# Anchor_G431.net
KiCad netlist of a schematic drawn in Altium Designer
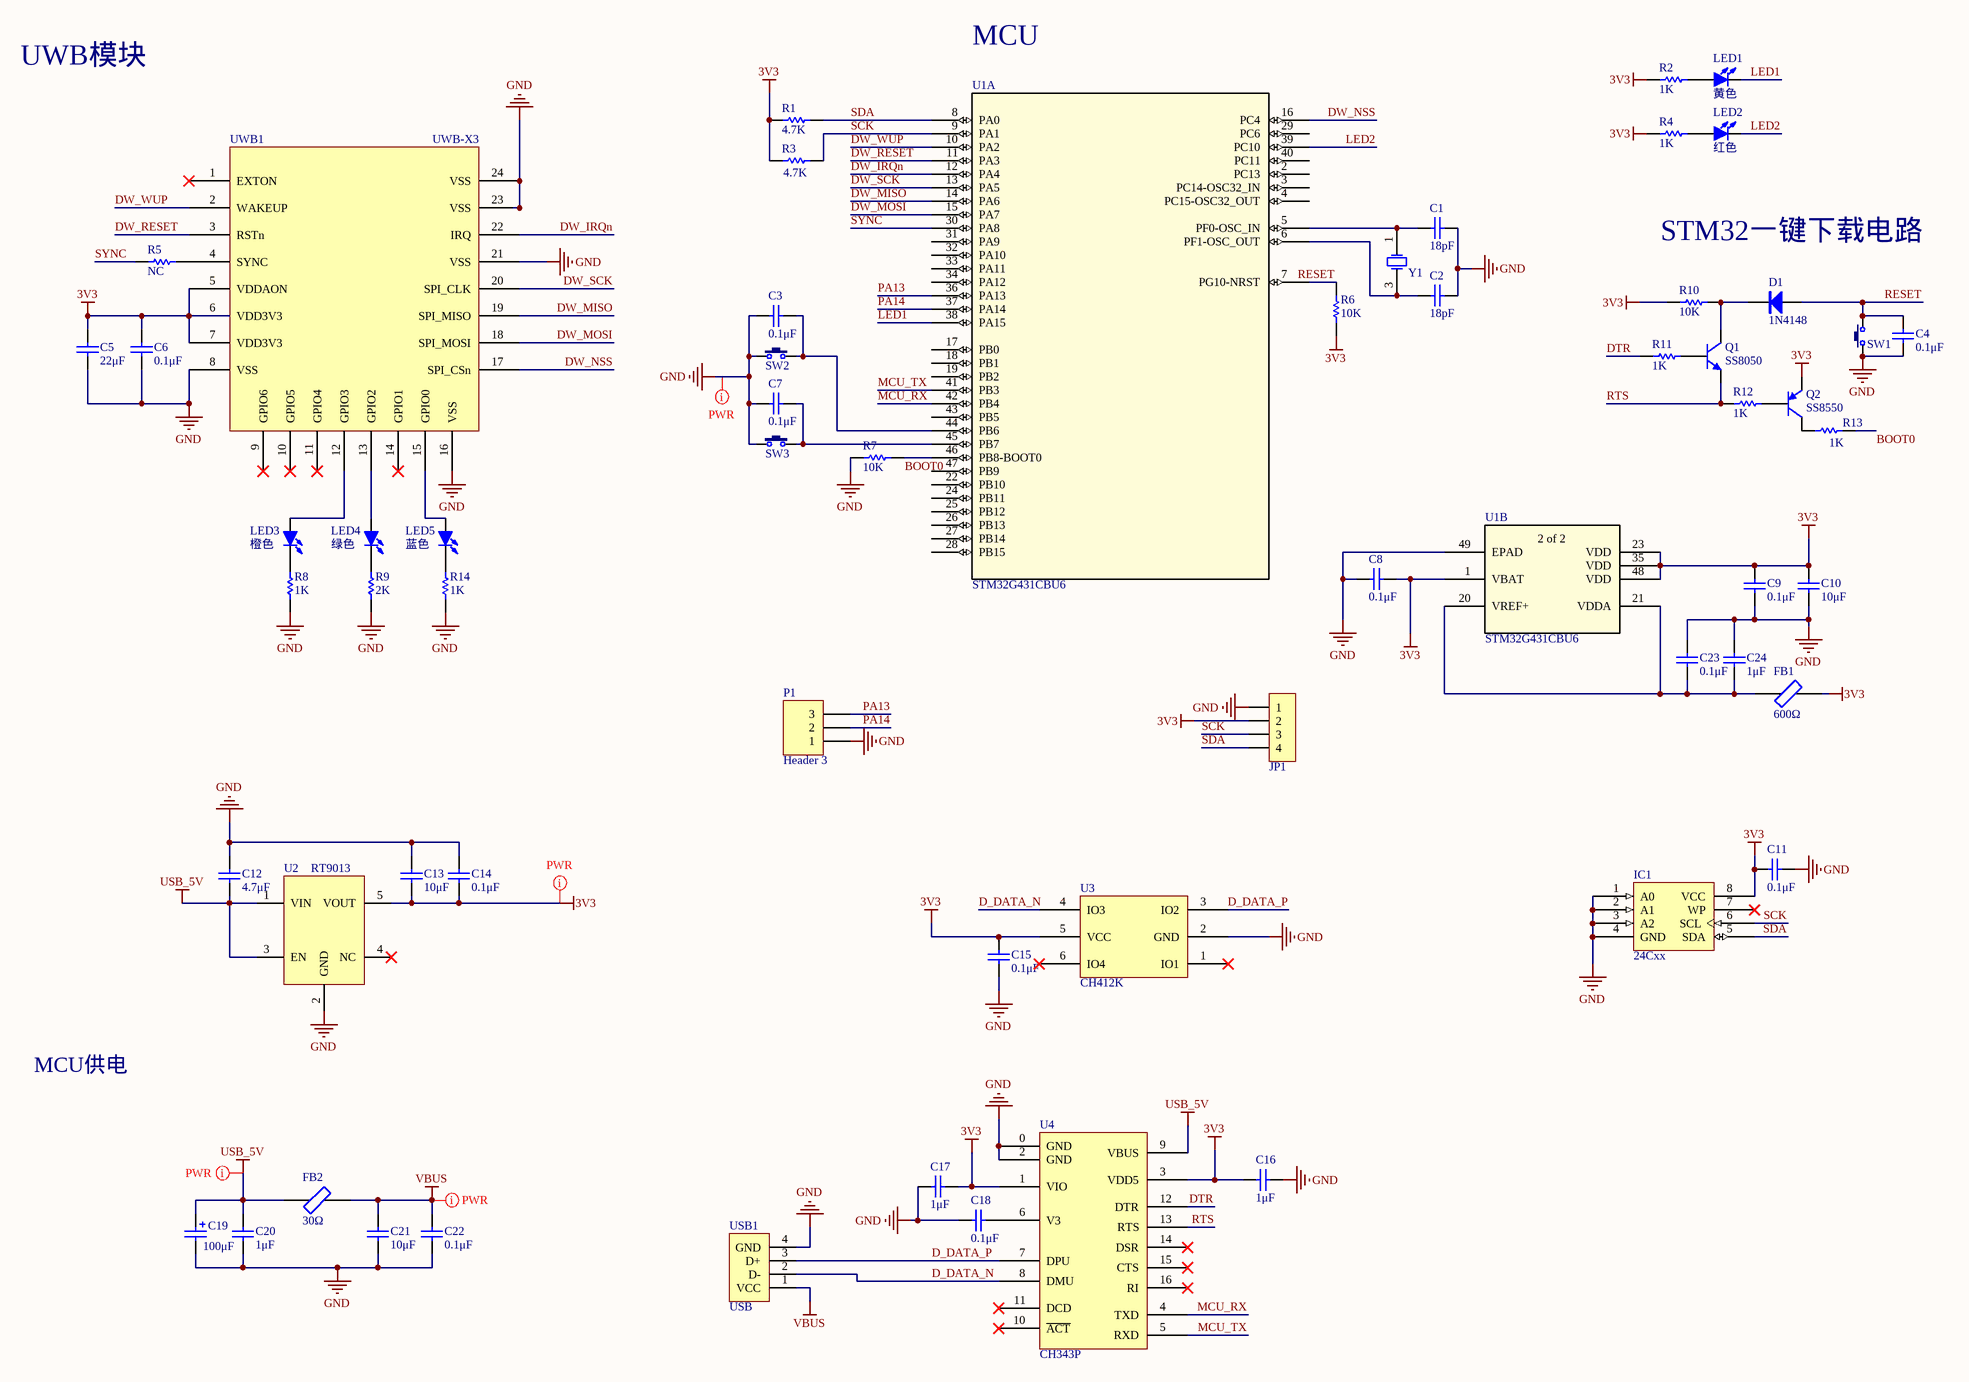
[diagram p0: Anchor_G431.SchDoc]

(export (version "E")
  (design (tool "Eeschema 10.0.6"))
  (components
    (comp (ref "C1")
      (value "18pF")
      (footprint "C 0603_L")
      (description "Capacitor")
      (fields (field (name "Comment") "Cap") (field (name "PUBLISHER") "Altium Limited"))
      (libsource (lib "Nixie") (part "Cap"))
    )
    (comp (ref "C2")
      (value "18pF")
      (footprint "C 0603_L")
      (description "Capacitor")
      (fields (field (name "Comment") "Cap") (field (name "PUBLISHER") "Altium Limited"))
      (libsource (lib "Nixie") (part "Cap"))
    )
    (comp (ref "C3")
      (value "0.1μF")
      (footprint "C 0603_L")
      (description "Capacitor")
      (fields (field (name "Comment") "Cap") (field (name "PUBLISHER") "Altium Limited"))
      (libsource (lib "Nixie") (part "Cap"))
    )
    (comp (ref "C4")
      (value "0.1μF")
      (footprint "C 0603_L")
      (description "Capacitor")
      (fields (field (name "Comment") "Cap") (field (name "PUBLISHER") "Altium Limited"))
      (libsource (lib "Nixie") (part "Cap"))
    )
    (comp (ref "C5")
      (value "22μF")
      (footprint "C 0603_L")
      (description "Capacitor")
      (fields (field (name "Comment") "Cap") (field (name "PUBLISHER") "Altium Limited"))
      (libsource (lib "Nixie") (part "Cap"))
    )
    (comp (ref "C6")
      (value "0.1μF")
      (footprint "C 0603_L")
      (description "Capacitor")
      (fields (field (name "Comment") "Cap") (field (name "PUBLISHER") "Altium Limited"))
      (libsource (lib "Nixie") (part "Cap"))
    )
    (comp (ref "C7")
      (value "0.1μF")
      (footprint "C 0603_L")
      (description "Capacitor")
      (fields (field (name "Comment") "Cap") (field (name "PUBLISHER") "Altium Limited"))
      (libsource (lib "Nixie") (part "Cap"))
    )
    (comp (ref "C8")
      (value "0.1μF")
      (footprint "C 0603_L")
      (description "Capacitor")
      (fields (field (name "Comment") "Cap") (field (name "PUBLISHER") "Altium Limited"))
      (libsource (lib "Nixie") (part "Cap"))
    )
    (comp (ref "C9")
      (value "0.1μF")
      (footprint "C 0603_L")
      (description "Capacitor")
      (fields (field (name "Comment") "Cap") (field (name "PUBLISHER") "Altium Limited"))
      (libsource (lib "Nixie") (part "Cap"))
    )
    (comp (ref "C10")
      (value "10μF")
      (footprint "C 0603_L")
      (description "Capacitor")
      (fields (field (name "Comment") "Cap") (field (name "PUBLISHER") "Altium Limited"))
      (libsource (lib "Nixie") (part "Cap"))
    )
    (comp (ref "C11")
      (value "0.1μF")
      (footprint "C 0603_L")
      (description "Capacitor")
      (fields (field (name "Comment") "Cap") (field (name "PUBLISHER") "Altium Limited"))
      (libsource (lib "Nixie") (part "Cap"))
    )
    (comp (ref "C12")
      (value "4.7μF")
      (footprint "C 0603_L")
      (description "Capacitor")
      (fields (field (name "Comment") "Cap") (field (name "PUBLISHER") "Altium Limited"))
      (libsource (lib "Nixie") (part "Cap"))
    )
    (comp (ref "C13")
      (value "10μF")
      (footprint "C 0603_L")
      (description "Capacitor")
      (fields (field (name "Comment") "Cap") (field (name "PUBLISHER") "Altium Limited"))
      (libsource (lib "Nixie") (part "Cap"))
    )
    (comp (ref "C14")
      (value "0.1μF")
      (footprint "C 0603_L")
      (description "Capacitor")
      (fields (field (name "Comment") "Cap") (field (name "PUBLISHER") "Altium Limited"))
      (libsource (lib "Nixie") (part "Cap"))
    )
    (comp (ref "C15")
      (value "0.1μF")
      (footprint "C 0603_L")
      (description "Capacitor")
      (fields (field (name "Comment") "Cap") (field (name "PUBLISHER") "Altium Limited"))
      (libsource (lib "Nixie") (part "Cap"))
    )
    (comp (ref "C16")
      (value "1μF")
      (footprint "C 0603_L")
      (description "Capacitor")
      (fields (field (name "Comment") "Cap") (field (name "PUBLISHER") "Altium Limited"))
      (libsource (lib "Nixie") (part "Cap"))
    )
    (comp (ref "C17")
      (value "1μF")
      (footprint "C 0603_L")
      (description "Capacitor")
      (fields (field (name "Comment") "Cap") (field (name "PUBLISHER") "Altium Limited"))
      (libsource (lib "Nixie") (part "Cap"))
    )
    (comp (ref "C18")
      (value "0.1μF")
      (footprint "C 0603_L")
      (description "Capacitor")
      (fields (field (name "Comment") "Cap") (field (name "PUBLISHER") "Altium Limited"))
      (libsource (lib "Nixie") (part "Cap"))
    )
    (comp (ref "C19")
      (value "100μF")
      (footprint "CM C(5*5.4)")
      (description "Polarized Capacitor (Radial)")
      (fields (field (name "Comment") "Cap Pol1") (field (name "PUBLISHER") "Altium Limited"))
      (libsource (lib "Nixie") (part "Cap Pol1"))
    )
    (comp (ref "C20")
      (value "1μF")
      (footprint "C 0603_L")
      (description "Capacitor")
      (fields (field (name "Comment") "Cap") (field (name "PUBLISHER") "Altium Limited"))
      (libsource (lib "Nixie") (part "Cap"))
    )
    (comp (ref "C21")
      (value "10μF")
      (footprint "C 0603_L")
      (description "Capacitor")
      (fields (field (name "Comment") "Cap") (field (name "PUBLISHER") "Altium Limited"))
      (libsource (lib "Nixie") (part "Cap"))
    )
    (comp (ref "C22")
      (value "0.1μF")
      (footprint "C 0603_L")
      (description "Capacitor")
      (fields (field (name "Comment") "Cap") (field (name "PUBLISHER") "Altium Limited"))
      (libsource (lib "Nixie") (part "Cap"))
    )
    (comp (ref "C23")
      (value "0.1μF")
      (footprint "C 0603_L")
      (description "Capacitor")
      (fields (field (name "Comment") "Cap") (field (name "PUBLISHER") "Altium Limited"))
      (libsource (lib "Nixie") (part "Cap"))
    )
    (comp (ref "C24")
      (value "1μF")
      (footprint "C 0603_L")
      (description "Capacitor")
      (fields (field (name "Comment") "Cap") (field (name "PUBLISHER") "Altium Limited"))
      (libsource (lib "Nixie") (part "Cap"))
    )
    (comp (ref "D1")
      (value "1N4148")
      (footprint "SOD-323")
      (description "开关二极管")
      (libsource (lib "Nixie") (part "1N4148"))
    )
    (comp (ref "FB1")
      (value "600Ω")
      (footprint "C 0603_L")
      (description "铁氧体磁珠")
      (fields (field (name "Comment") "Ferrite bead"))
      (libsource (lib "Nixie") (part "Ferrite bead"))
    )
    (comp (ref "FB2")
      (value "30Ω")
      (footprint "C 0603_L")
      (description "铁氧体磁珠")
      (fields (field (name "Comment") "Ferrite bead"))
      (libsource (lib "Nixie") (part "Ferrite bead"))
    )
    (comp (ref "IC1")
      (value "24Cxx")
      (footprint "SOP8_L")
      (description "外置EEPROM")
      (fields (field (name "版权归属") "封装库来自淘宝 ID：黄晶宝石"))
      (libsource (lib "Nixie") (part "24Cxx"))
    )
    (comp (ref "JP1")
      (value "HDR-1X4")
      (footprint "HDR2.54-LI-4P")
      (description "4P接插件")
      (fields (field (name "版权归属") "封装库来自淘宝 ID：黄晶宝石"))
      (libsource (lib "Nixie") (part "Header 4"))
    )
    (comp (ref "LED1")
      (value "黄色")
      (footprint "LED 0805G")
      (description "贴片LED")
      (fields (field (name "版权归属") "封装库来自淘宝 ID：黄晶宝石"))
      (libsource (lib "Nixie") (part "LED-SMD"))
    )
    (comp (ref "LED2")
      (value "红色")
      (footprint "LED 0805R")
      (description "贴片LED")
      (fields (field (name "版权归属") "封装库来自淘宝 ID：黄晶宝石"))
      (libsource (lib "Nixie") (part "LED-SMD"))
    )
    (comp (ref "LED3")
      (value "橙色")
      (footprint "LED 0805G")
      (description "贴片LED")
      (fields (field (name "版权归属") "封装库来自淘宝 ID：黄晶宝石"))
      (libsource (lib "Nixie") (part "LED-SMD"))
    )
    (comp (ref "LED4")
      (value "绿色")
      (footprint "LED 0805G")
      (description "贴片LED")
      (fields (field (name "版权归属") "封装库来自淘宝 ID：黄晶宝石"))
      (libsource (lib "Nixie") (part "LED-SMD"))
    )
    (comp (ref "LED5")
      (value "蓝色")
      (footprint "LED 0805G")
      (description "贴片LED")
      (fields (field (name "版权归属") "封装库来自淘宝 ID：黄晶宝石"))
      (libsource (lib "Nixie") (part "LED-SMD"))
    )
    (comp (ref "P1")
      (value "Header 3")
      (footprint "HDR2.54-LI-3P")
      (description "Header, 3-Pin")
      (fields (field (name "PUBLISHER") "Altium Limited"))
      (libsource (lib "Miscellaneous Connectors") (part "Header 3"))
    )
    (comp (ref "Q1")
      (value "SS8050")
      (footprint "SOT-23-3L")
      (description "高频放大-NPN型")
      (fields (field (name "版权归属") "封装库来自淘宝 ID：黄晶宝石"))
      (libsource (lib "Nixie") (part "8050-SMD"))
    )
    (comp (ref "Q2")
      (value "SS8550")
      (footprint "SOT-23-3L")
      (description "高频放大-PNP型")
      (fields (field (name "版权归属") "封装库来自淘宝 ID：黄晶宝石"))
      (libsource (lib "Nixie") (part "8550-SMD"))
    )
    (comp (ref "R1")
      (value "4.7K")
      (footprint "R 0603_L")
      (description "Resistor")
      (fields (field (name "PUBLISHER") "Altium Limited"))
      (libsource (lib "Nixie") (part "Resistor"))
    )
    (comp (ref "R2")
      (value "1K")
      (footprint "R 0603_L")
      (description "Resistor")
      (fields (field (name "PUBLISHER") "Altium Limited"))
      (libsource (lib "Nixie") (part "Resistor"))
    )
    (comp (ref "R3")
      (value "4.7K")
      (footprint "R 0603_L")
      (description "Resistor")
      (fields (field (name "PUBLISHER") "Altium Limited"))
      (libsource (lib "Nixie") (part "Resistor"))
    )
    (comp (ref "R4")
      (value "1K")
      (footprint "R 0603_L")
      (description "Resistor")
      (fields (field (name "PUBLISHER") "Altium Limited"))
      (libsource (lib "Nixie") (part "Resistor"))
    )
    (comp (ref "R5")
      (value "NC")
      (footprint "R 0603_L")
      (description "Resistor")
      (fields (field (name "PUBLISHER") "Altium Limited"))
      (libsource (lib "Nixie") (part "Resistor"))
    )
    (comp (ref "R6")
      (value "10K")
      (footprint "R 0603_L")
      (description "Resistor")
      (fields (field (name "PUBLISHER") "Altium Limited"))
      (libsource (lib "Nixie") (part "Resistor"))
    )
    (comp (ref "R7")
      (value "10K")
      (footprint "R 0603_L")
      (description "Resistor")
      (fields (field (name "PUBLISHER") "Altium Limited"))
      (libsource (lib "Nixie") (part "Resistor"))
    )
    (comp (ref "R8")
      (value "1K")
      (footprint "R 0603_L")
      (description "Resistor")
      (fields (field (name "PUBLISHER") "Altium Limited"))
      (libsource (lib "Nixie") (part "Resistor"))
    )
    (comp (ref "R9")
      (value "2K")
      (footprint "R 0603_L")
      (description "Resistor")
      (fields (field (name "PUBLISHER") "Altium Limited"))
      (libsource (lib "Nixie") (part "Resistor"))
    )
    (comp (ref "R10")
      (value "10K")
      (footprint "R 0603_L")
      (description "Resistor")
      (fields (field (name "PUBLISHER") "Altium Limited"))
      (libsource (lib "Nixie") (part "Resistor"))
    )
    (comp (ref "R11")
      (value "1K")
      (footprint "R 0603_L")
      (description "Resistor")
      (fields (field (name "PUBLISHER") "Altium Limited"))
      (libsource (lib "Nixie") (part "Resistor"))
    )
    (comp (ref "R12")
      (value "1K")
      (footprint "R 0603_L")
      (description "Resistor")
      (fields (field (name "PUBLISHER") "Altium Limited"))
      (libsource (lib "Nixie") (part "Resistor"))
    )
    (comp (ref "R13")
      (value "1K")
      (footprint "R 0603_L")
      (description "Resistor")
      (fields (field (name "PUBLISHER") "Altium Limited"))
      (libsource (lib "Nixie") (part "Resistor"))
    )
    (comp (ref "R14")
      (value "1K")
      (footprint "R 0603_L")
      (description "Resistor")
      (fields (field (name "PUBLISHER") "Altium Limited"))
      (libsource (lib "Nixie") (part "Resistor"))
    )
    (comp (ref "SW1")
      (value "3x6x5")
      (footprint "TSW SMD-3*6*2.5")
      (description "3x6轻触开关")
      (fields (field (name "版权归属") "封装库来自淘宝 ID：黄晶宝石"))
      (libsource (lib "Nixie") (part "TSW 3x6"))
    )
    (comp (ref "SW2")
      (value "3x6x5")
      (footprint "TSW SMD-3*6*2.5")
      (description "3x6轻触开关")
      (fields (field (name "版权归属") "封装库来自淘宝 ID：黄晶宝石"))
      (libsource (lib "") (part "TSW 3x6_1"))
    )
    (comp (ref "SW3")
      (value "3x6x5")
      (footprint "TSW SMD-3*6*2.5")
      (description "3x6轻触开关")
      (fields (field (name "版权归属") "封装库来自淘宝 ID：黄晶宝石"))
      (libsource (lib "") (part "TSW 3x6_1"))
    )
    (comp (ref "U1")
      (value "STM32G431CBU6")
      (footprint "UFQFPN-48_7X7X0P55MM")
      (description "No Description Available")
      (fields (field (name "COPYRIGHT") "Copyright (C) 2023 Ultra Librarian. All rights reserved."))
      (libsource (lib "Nixie") (part "STM32G431CBU6"))
    )
    (comp (ref "U2")
      (value "RT9013")
      (footprint "SOT23-5L")
      (description "LDO")
      (libsource (lib "HandHeld_terminal") (part "RT9013"))
    )
    (comp (ref "U3")
      (value "CH412K")
      (footprint "SOT-363")
      (description "四路ESD保护")
      (libsource (lib "Nixie") (part "CH412K"))
    )
    (comp (ref "U4")
      (value "CH343P")
      (footprint "QFN16")
      (description "USB转串口")
      (libsource (lib "Nixie") (part "CH343"))
    )
    (comp (ref "USB1")
      (value "USB")
      (footprint "USB_A/P_B")
      (description "USB-A型公接口")
      (fields (field (name "版权归属") "封装库来自淘宝卖家 ID：黄晶宝石"))
      (libsource (lib "Nixie") (part "USB-A/P"))
    )
    (comp (ref "UWB1")
      (value "UWB-X3")
      (footprint "UWB-X3-MAX-IPEX")
      (libsource (lib "Nixie") (part "UWB-X3(DWM3000)"))
    )
    (comp (ref "Y1")
      (value "8MHz ±20ppm 20pF")
      (footprint "OSC 3225-4P")
      (description "贴片晶振")
      (libsource (lib "HandHeld_terminal") (part "SMD-5032_2P 8MHz 20ppm 20pF"))
    )
  )
  (nets
    (net (code "1") (name "/BOOT0") (class "Default")
      (node (ref "R13") (pin "2") (pinfunction "2_2") (pintype "passive"))
      (node (ref "R7") (pin "2") (pinfunction "2_2") (pintype "passive"))
      (node (ref "U1") (pin "46") (pinfunction "PB8-BOOT0_46") (pintype "bidirectional"))
    )
    (net (code "2") (name "/DTR") (class "Default")
      (node (ref "R11") (pin "1") (pinfunction "1_1") (pintype "passive"))
      (node (ref "U4") (pin "12") (pinfunction "DTR_12") (pintype "passive"))
    )
    (net (code "3") (name "/DW_IRQn") (class "Default")
      (node (ref "U1") (pin "12") (pinfunction "PA4_12") (pintype "bidirectional"))
      (node (ref "UWB1") (pin "22") (pinfunction "IRQ_22") (pintype "passive"))
    )
    (net (code "4") (name "/DW_MISO") (class "Default")
      (node (ref "U1") (pin "14") (pinfunction "PA6_14") (pintype "bidirectional"))
      (node (ref "UWB1") (pin "19") (pinfunction "SPI_MISO_19") (pintype "passive"))
    )
    (net (code "5") (name "/DW_MOSI") (class "Default")
      (node (ref "U1") (pin "15") (pinfunction "PA7_15") (pintype "bidirectional"))
      (node (ref "UWB1") (pin "18") (pinfunction "SPI_MOSI_18") (pintype "passive"))
    )
    (net (code "6") (name "/DW_NSS") (class "Default")
      (node (ref "U1") (pin "16") (pinfunction "PC4_16") (pintype "bidirectional"))
      (node (ref "UWB1") (pin "17") (pinfunction "SPI_CSn_17") (pintype "passive"))
    )
    (net (code "7") (name "/DW_RESET") (class "Default")
      (node (ref "U1") (pin "11") (pinfunction "PA3_11") (pintype "bidirectional"))
      (node (ref "UWB1") (pin "3") (pinfunction "RSTn_3") (pintype "passive"))
    )
    (net (code "8") (name "/DW_SCK") (class "Default")
      (node (ref "U1") (pin "13") (pinfunction "PA5_13") (pintype "bidirectional"))
      (node (ref "UWB1") (pin "20") (pinfunction "SPI_CLK_20") (pintype "passive"))
    )
    (net (code "9") (name "/DW_WUP") (class "Default")
      (node (ref "U1") (pin "10") (pinfunction "PA2_10") (pintype "bidirectional"))
      (node (ref "UWB1") (pin "2") (pinfunction "WAKEUP_2") (pintype "passive"))
    )
    (net (code "10") (name "/D_DATA_N") (class "Default")
      (node (ref "U3") (pin "4") (pinfunction "IO3_4") (pintype "passive"))
      (node (ref "U4") (pin "8") (pinfunction "DMU_8") (pintype "passive"))
      (node (ref "USB1") (pin "2") (pinfunction "D-_2") (pintype "passive"))
    )
    (net (code "11") (name "/D_DATA_P") (class "Default")
      (node (ref "U3") (pin "3") (pinfunction "IO2_3") (pintype "passive"))
      (node (ref "U4") (pin "7") (pinfunction "DPU_7") (pintype "passive"))
      (node (ref "USB1") (pin "3") (pinfunction "D+_3") (pintype "passive"))
    )
    (net (code "12") (name "/LED1") (class "Default")
      (node (ref "LED1") (pin "2") (pinfunction "K_2") (pintype "passive"))
      (node (ref "U1") (pin "38") (pinfunction "PA15_38") (pintype "bidirectional"))
    )
    (net (code "13") (name "/LED2") (class "Default")
      (node (ref "LED2") (pin "2") (pinfunction "K_2") (pintype "passive"))
      (node (ref "U1") (pin "39") (pinfunction "PC10_39") (pintype "bidirectional"))
    )
    (net (code "14") (name "/MCU_RX") (class "Default")
      (node (ref "U1") (pin "42") (pinfunction "PB4_42") (pintype "bidirectional"))
      (node (ref "U4") (pin "4") (pinfunction "TXD_4") (pintype "passive"))
    )
    (net (code "15") (name "/MCU_TX") (class "Default")
      (node (ref "U1") (pin "41") (pinfunction "PB3_41") (pintype "bidirectional"))
      (node (ref "U4") (pin "5") (pinfunction "RXD_5") (pintype "passive"))
    )
    (net (code "16") (name "/PA13") (class "Default")
      (node (ref "P1") (pin "3") (pinfunction "3_3") (pintype "passive"))
      (node (ref "U1") (pin "36") (pinfunction "PA13_36") (pintype "bidirectional"))
    )
    (net (code "17") (name "/PA14") (class "Default")
      (node (ref "P1") (pin "2") (pinfunction "2_2") (pintype "passive"))
      (node (ref "U1") (pin "37") (pinfunction "PA14_37") (pintype "bidirectional"))
    )
    (net (code "18") (name "/RESET") (class "Default")
      (node (ref "C4") (pin "2") (pinfunction "2_2") (pintype "passive"))
      (node (ref "D1") (pin "1") (pinfunction "A_1") (pintype "passive"))
      (node (ref "R6") (pin "1") (pinfunction "1_1") (pintype "passive"))
      (node (ref "SW1") (pin "2") (pinfunction "2_2") (pintype "passive"))
      (node (ref "U1") (pin "7") (pinfunction "PG10-NRST_7") (pintype "bidirectional"))
    )
    (net (code "19") (name "/RTS") (class "Default")
      (node (ref "Q1") (pin "2") (pinfunction "E_2") (pintype "passive"))
      (node (ref "R12") (pin "1") (pinfunction "1_1") (pintype "passive"))
      (node (ref "U4") (pin "13") (pinfunction "RTS_13") (pintype "passive"))
    )
    (net (code "20") (name "/SCK") (class "Default")
      (node (ref "IC1") (pin "6") (pinfunction "SCL_6") (pintype "input"))
      (node (ref "JP1") (pin "3") (pinfunction "3_3") (pintype "passive"))
      (node (ref "R3") (pin "2") (pinfunction "2_2") (pintype "passive"))
      (node (ref "U1") (pin "9") (pinfunction "PA1_9") (pintype "bidirectional"))
    )
    (net (code "21") (name "/SDA") (class "Default")
      (node (ref "IC1") (pin "5") (pinfunction "SDA_5") (pintype "bidirectional"))
      (node (ref "JP1") (pin "4") (pinfunction "4_4") (pintype "passive"))
      (node (ref "R1") (pin "2") (pinfunction "2_2") (pintype "passive"))
      (node (ref "U1") (pin "8") (pinfunction "PA0_8") (pintype "bidirectional"))
    )
    (net (code "22") (name "/SYNC") (class "Default")
      (node (ref "R5") (pin "1") (pinfunction "1_1") (pintype "passive"))
      (node (ref "U1") (pin "30") (pinfunction "PA8_30") (pintype "bidirectional"))
    )
    (net (code "23") (name "3V3") (class "Default")
      (node (ref "C10") (pin "2") (pinfunction "2_2") (pintype "passive"))
      (node (ref "C11") (pin "2") (pinfunction "2_2") (pintype "passive"))
      (node (ref "C13") (pin "1") (pinfunction "1_1") (pintype "passive"))
      (node (ref "C14") (pin "1") (pinfunction "1_1") (pintype "passive"))
      (node (ref "C15") (pin "2") (pinfunction "2_2") (pintype "passive"))
      (node (ref "C16") (pin "1") (pinfunction "1_1") (pintype "passive"))
      (node (ref "C17") (pin "2") (pinfunction "2_2") (pintype "passive"))
      (node (ref "C5") (pin "2") (pinfunction "2_2") (pintype "passive"))
      (node (ref "C6") (pin "1") (pinfunction "1_1") (pintype "passive"))
      (node (ref "C8") (pin "1") (pinfunction "1_1") (pintype "passive"))
      (node (ref "C9") (pin "2") (pinfunction "2_2") (pintype "passive"))
      (node (ref "FB1") (pin "2") (pinfunction "2_2") (pintype "passive"))
      (node (ref "IC1") (pin "8") (pinfunction "VCC_8") (pintype "power_in"))
      (node (ref "JP1") (pin "2") (pinfunction "2_2") (pintype "passive"))
      (node (ref "Q2") (pin "2") (pinfunction "E_2") (pintype "passive"))
      (node (ref "R1") (pin "1") (pinfunction "1_1") (pintype "passive"))
      (node (ref "R10") (pin "1") (pinfunction "1_1") (pintype "passive"))
      (node (ref "R2") (pin "2") (pinfunction "2_2") (pintype "passive"))
      (node (ref "R3") (pin "1") (pinfunction "1_1") (pintype "passive"))
      (node (ref "R4") (pin "2") (pinfunction "2_2") (pintype "passive"))
      (node (ref "R6") (pin "2") (pinfunction "2_2") (pintype "passive"))
      (node (ref "U1") (pin "1") (pinfunction "VBAT_1") (pintype "power_in"))
      (node (ref "U1") (pin "23") (pinfunction "VDD_23") (pintype "power_in"))
      (node (ref "U1") (pin "35") (pinfunction "VDD_35") (pintype "power_in"))
      (node (ref "U1") (pin "48") (pinfunction "VDD_48") (pintype "power_in"))
      (node (ref "U2") (pin "5") (pinfunction "VOUT_5") (pintype "passive"))
      (node (ref "U3") (pin "5") (pinfunction "VCC_5") (pintype "passive"))
      (node (ref "U4") (pin "1") (pinfunction "VIO_1") (pintype "passive"))
      (node (ref "U4") (pin "3") (pinfunction "VDD5_3") (pintype "passive"))
      (node (ref "UWB1") (pin "5") (pinfunction "VDDAON_5") (pintype "passive"))
      (node (ref "UWB1") (pin "6") (pinfunction "VDD3V3_6") (pintype "passive"))
      (node (ref "UWB1") (pin "7") (pinfunction "VDD3V3_7") (pintype "passive"))
    )
    (net (code "24") (name "GND") (class "Default")
      (node (ref "C1") (pin "1") (pinfunction "1_1") (pintype "passive"))
      (node (ref "C10") (pin "1") (pinfunction "1_1") (pintype "passive"))
      (node (ref "C11") (pin "1") (pinfunction "1_1") (pintype "passive"))
      (node (ref "C12") (pin "2") (pinfunction "2_2") (pintype "passive"))
      (node (ref "C13") (pin "2") (pinfunction "2_2") (pintype "passive"))
      (node (ref "C14") (pin "2") (pinfunction "2_2") (pintype "passive"))
      (node (ref "C15") (pin "1") (pinfunction "1_1") (pintype "passive"))
      (node (ref "C16") (pin "2") (pinfunction "2_2") (pintype "passive"))
      (node (ref "C17") (pin "1") (pinfunction "1_1") (pintype "passive"))
      (node (ref "C18") (pin "1") (pinfunction "1_1") (pintype "passive"))
      (node (ref "C19") (pin "2") (pinfunction "2_2") (pintype "passive"))
      (node (ref "C2") (pin "1") (pinfunction "1_1") (pintype "passive"))
      (node (ref "C20") (pin "1") (pinfunction "1_1") (pintype "passive"))
      (node (ref "C21") (pin "1") (pinfunction "1_1") (pintype "passive"))
      (node (ref "C22") (pin "1") (pinfunction "1_1") (pintype "passive"))
      (node (ref "C23") (pin "2") (pinfunction "2_2") (pintype "passive"))
      (node (ref "C24") (pin "2") (pinfunction "2_2") (pintype "passive"))
      (node (ref "C3") (pin "2") (pinfunction "2_2") (pintype "passive"))
      (node (ref "C4") (pin "1") (pinfunction "1_1") (pintype "passive"))
      (node (ref "C5") (pin "1") (pinfunction "1_1") (pintype "passive"))
      (node (ref "C6") (pin "2") (pinfunction "2_2") (pintype "passive"))
      (node (ref "C7") (pin "2") (pinfunction "2_2") (pintype "passive"))
      (node (ref "C8") (pin "2") (pinfunction "2_2") (pintype "passive"))
      (node (ref "C9") (pin "1") (pinfunction "1_1") (pintype "passive"))
      (node (ref "IC1") (pin "1") (pinfunction "A0_1") (pintype "input"))
      (node (ref "IC1") (pin "2") (pinfunction "A1_2") (pintype "input"))
      (node (ref "IC1") (pin "3") (pinfunction "A2_3") (pintype "input"))
      (node (ref "IC1") (pin "4") (pinfunction "GND_4") (pintype "passive"))
      (node (ref "JP1") (pin "1") (pinfunction "1_1") (pintype "passive"))
      (node (ref "P1") (pin "1") (pinfunction "1_1") (pintype "passive"))
      (node (ref "R14") (pin "2") (pinfunction "2_2") (pintype "passive"))
      (node (ref "R7") (pin "1") (pinfunction "1_1") (pintype "passive"))
      (node (ref "R8") (pin "2") (pinfunction "2_2") (pintype "passive"))
      (node (ref "R9") (pin "2") (pinfunction "2_2") (pintype "passive"))
      (node (ref "SW1") (pin "1") (pinfunction "1_1") (pintype "passive"))
      (node (ref "SW2") (pin "1") (pinfunction "1_1") (pintype "passive"))
      (node (ref "SW3") (pin "1") (pinfunction "1_1") (pintype "passive"))
      (node (ref "U1") (pin "49") (pinfunction "EPAD_49") (pintype "passive"))
      (node (ref "U2") (pin "2") (pinfunction "GND_2") (pintype "passive"))
      (node (ref "U3") (pin "2") (pinfunction "GND_2") (pintype "passive"))
      (node (ref "U4") (pin "0") (pinfunction "GND_0") (pintype "passive"))
      (node (ref "U4") (pin "2") (pinfunction "GND_2") (pintype "passive"))
      (node (ref "USB1") (pin "4") (pinfunction "GND_4") (pintype "passive"))
      (node (ref "UWB1") (pin "16") (pinfunction "VSS_16") (pintype "passive"))
      (node (ref "UWB1") (pin "21") (pinfunction "VSS_21") (pintype "passive"))
      (node (ref "UWB1") (pin "23") (pinfunction "VSS_23") (pintype "passive"))
      (node (ref "UWB1") (pin "24") (pinfunction "VSS_24") (pintype "passive"))
      (node (ref "UWB1") (pin "8") (pinfunction "VSS_8") (pintype "passive"))
    )
    (net (code "25") (name "Net-(D1-K)") (class "Default")
      (node (ref "D1") (pin "2") (pinfunction "K_2") (pintype "passive"))
      (node (ref "Q1") (pin "3") (pinfunction "C_3") (pintype "passive"))
      (node (ref "R10") (pin "2") (pinfunction "2_2") (pintype "passive"))
    )
    (net (code "26") (name "Net-(LED1-A)") (class "Default")
      (node (ref "LED1") (pin "1") (pinfunction "A_1") (pintype "passive"))
      (node (ref "R2") (pin "1") (pinfunction "1_1") (pintype "passive"))
    )
    (net (code "27") (name "Net-(LED2-A)") (class "Default")
      (node (ref "LED2") (pin "1") (pinfunction "A_1") (pintype "passive"))
      (node (ref "R4") (pin "1") (pinfunction "1_1") (pintype "passive"))
    )
    (net (code "28") (name "Net-(LED3-A)") (class "Default")
      (node (ref "LED3") (pin "1") (pinfunction "A_1") (pintype "passive"))
      (node (ref "UWB1") (pin "12") (pinfunction "GPIO3_12") (pintype "passive"))
    )
    (net (code "29") (name "Net-(LED3-K)") (class "Default")
      (node (ref "LED3") (pin "2") (pinfunction "K_2") (pintype "passive"))
      (node (ref "R8") (pin "1") (pinfunction "1_1") (pintype "passive"))
    )
    (net (code "30") (name "Net-(LED4-A)") (class "Default")
      (node (ref "LED4") (pin "1") (pinfunction "A_1") (pintype "passive"))
      (node (ref "UWB1") (pin "13") (pinfunction "GPIO2_13") (pintype "passive"))
    )
    (net (code "31") (name "Net-(LED4-K)") (class "Default")
      (node (ref "LED4") (pin "2") (pinfunction "K_2") (pintype "passive"))
      (node (ref "R9") (pin "1") (pinfunction "1_1") (pintype "passive"))
    )
    (net (code "32") (name "Net-(LED5-A)") (class "Default")
      (node (ref "LED5") (pin "1") (pinfunction "A_1") (pintype "passive"))
      (node (ref "UWB1") (pin "15") (pinfunction "GPIO0_15") (pintype "passive"))
    )
    (net (code "33") (name "Net-(LED5-K)") (class "Default")
      (node (ref "LED5") (pin "2") (pinfunction "K_2") (pintype "passive"))
      (node (ref "R14") (pin "1") (pinfunction "1_1") (pintype "passive"))
    )
    (net (code "34") (name "Net-(Q1-B)") (class "Default")
      (node (ref "Q1") (pin "1") (pinfunction "B_1") (pintype "passive"))
      (node (ref "R11") (pin "2") (pinfunction "2_2") (pintype "passive"))
    )
    (net (code "35") (name "Net-(Q2-B)") (class "Default")
      (node (ref "Q2") (pin "1") (pinfunction "B_1") (pintype "passive"))
      (node (ref "R12") (pin "2") (pinfunction "2_2") (pintype "passive"))
    )
    (net (code "36") (name "Net-(Q2-C)") (class "Default")
      (node (ref "Q2") (pin "3") (pinfunction "C_3") (pintype "passive"))
      (node (ref "R13") (pin "1") (pinfunction "1_1") (pintype "passive"))
    )
    (net (code "37") (name "Net-(U1A-PB6)") (class "Default")
      (node (ref "C3") (pin "1") (pinfunction "1_1") (pintype "passive"))
      (node (ref "SW2") (pin "2") (pinfunction "2_2") (pintype "passive"))
      (node (ref "U1") (pin "44") (pinfunction "PB6_44") (pintype "bidirectional"))
    )
    (net (code "38") (name "Net-(U1A-PB7)") (class "Default")
      (node (ref "C7") (pin "1") (pinfunction "1_1") (pintype "passive"))
      (node (ref "SW3") (pin "2") (pinfunction "2_2") (pintype "passive"))
      (node (ref "U1") (pin "45") (pinfunction "PB7_45") (pintype "bidirectional"))
    )
    (net (code "39") (name "Net-(U1A-PF0-OSC_IN)") (class "Default")
      (node (ref "C1") (pin "2") (pinfunction "2_2") (pintype "passive"))
      (node (ref "U1") (pin "5") (pinfunction "PF0-OSC_IN_5") (pintype "bidirectional"))
      (node (ref "Y1") (pin "1") (pinfunction "OSC1_1") (pintype "passive"))
    )
    (net (code "40") (name "Net-(U1A-PF1-OSC_OUT)") (class "Default")
      (node (ref "C2") (pin "2") (pinfunction "2_2") (pintype "passive"))
      (node (ref "U1") (pin "6") (pinfunction "PF1-OSC_OUT_6") (pintype "bidirectional"))
      (node (ref "Y1") (pin "3") (pinfunction "OSC2_3") (pintype "passive"))
    )
    (net (code "41") (name "Net-(U1B-VDDA)") (class "Default")
      (node (ref "C23") (pin "1") (pinfunction "1_1") (pintype "passive"))
      (node (ref "C24") (pin "1") (pinfunction "1_1") (pintype "passive"))
      (node (ref "FB1") (pin "1") (pinfunction "1_1") (pintype "passive"))
      (node (ref "U1") (pin "20") (pinfunction "VREF+_20") (pintype "power_in"))
      (node (ref "U1") (pin "21") (pinfunction "VDDA_21") (pintype "power_in"))
    )
    (net (code "42") (name "Net-(U4-V3)") (class "Default")
      (node (ref "C18") (pin "2") (pinfunction "2_2") (pintype "passive"))
      (node (ref "U4") (pin "6") (pinfunction "V3_6") (pintype "passive"))
    )
    (net (code "43") (name "Net-(UWB1-SYNC)") (class "Default")
      (node (ref "R5") (pin "2") (pinfunction "2_2") (pintype "passive"))
      (node (ref "UWB1") (pin "4") (pinfunction "SYNC_4") (pintype "passive"))
    )
    (net (code "44") (name "USB_5V") (class "Default")
      (node (ref "C12") (pin "1") (pinfunction "1_1") (pintype "passive"))
      (node (ref "C19") (pin "1") (pinfunction "1_1") (pintype "passive"))
      (node (ref "C20") (pin "2") (pinfunction "2_2") (pintype "passive"))
      (node (ref "FB2") (pin "1") (pinfunction "1_1") (pintype "passive"))
      (node (ref "U2") (pin "1") (pinfunction "VIN_1") (pintype "passive"))
      (node (ref "U2") (pin "3") (pinfunction "EN_3") (pintype "passive"))
      (node (ref "U4") (pin "9") (pinfunction "VBUS_9") (pintype "passive"))
    )
    (net (code "45") (name "VBUS") (class "Default")
      (node (ref "C21") (pin "2") (pinfunction "2_2") (pintype "passive"))
      (node (ref "C22") (pin "2") (pinfunction "2_2") (pintype "passive"))
      (node (ref "FB2") (pin "2") (pinfunction "2_2") (pintype "passive"))
      (node (ref "USB1") (pin "1") (pinfunction "VCC_1") (pintype "passive"))
    )
    (net (code "46") (name "unconnected-(IC1-WP-Pad7)") (class "Default")
      (node (ref "IC1") (pin "7") (pinfunction "WP_7") (pintype "passive+no_connect"))
    )
    (net (code "47") (name "unconnected-(U1A-PA9-Pad31)") (class "Default")
      (node (ref "U1") (pin "31") (pinfunction "PA9_31") (pintype "bidirectional"))
    )
    (net (code "48") (name "unconnected-(U1A-PA10-Pad32)") (class "Default")
      (node (ref "U1") (pin "32") (pinfunction "PA10_32") (pintype "bidirectional"))
    )
    (net (code "49") (name "unconnected-(U1A-PA11-Pad33)") (class "Default")
      (node (ref "U1") (pin "33") (pinfunction "PA11_33") (pintype "bidirectional"))
    )
    (net (code "50") (name "unconnected-(U1A-PA12-Pad34)") (class "Default")
      (node (ref "U1") (pin "34") (pinfunction "PA12_34") (pintype "bidirectional"))
    )
    (net (code "51") (name "unconnected-(U1A-PB0-Pad17)") (class "Default")
      (node (ref "U1") (pin "17") (pinfunction "PB0_17") (pintype "bidirectional"))
    )
    (net (code "52") (name "unconnected-(U1A-PB1-Pad18)") (class "Default")
      (node (ref "U1") (pin "18") (pinfunction "PB1_18") (pintype "bidirectional"))
    )
    (net (code "53") (name "unconnected-(U1A-PB2-Pad19)") (class "Default")
      (node (ref "U1") (pin "19") (pinfunction "PB2_19") (pintype "bidirectional"))
    )
    (net (code "54") (name "unconnected-(U1A-PB5-Pad43)") (class "Default")
      (node (ref "U1") (pin "43") (pinfunction "PB5_43") (pintype "bidirectional"))
    )
    (net (code "55") (name "unconnected-(U1A-PB9-Pad47)") (class "Default")
      (node (ref "U1") (pin "47") (pinfunction "PB9_47") (pintype "bidirectional"))
    )
    (net (code "56") (name "unconnected-(U1A-PB10-Pad22)") (class "Default")
      (node (ref "U1") (pin "22") (pinfunction "PB10_22") (pintype "bidirectional"))
    )
    (net (code "57") (name "unconnected-(U1A-PB11-Pad24)") (class "Default")
      (node (ref "U1") (pin "24") (pinfunction "PB11_24") (pintype "bidirectional"))
    )
    (net (code "58") (name "unconnected-(U1A-PB12-Pad25)") (class "Default")
      (node (ref "U1") (pin "25") (pinfunction "PB12_25") (pintype "bidirectional"))
    )
    (net (code "59") (name "unconnected-(U1A-PB13-Pad26)") (class "Default")
      (node (ref "U1") (pin "26") (pinfunction "PB13_26") (pintype "bidirectional"))
    )
    (net (code "60") (name "unconnected-(U1A-PB14-Pad27)") (class "Default")
      (node (ref "U1") (pin "27") (pinfunction "PB14_27") (pintype "bidirectional"))
    )
    (net (code "61") (name "unconnected-(U1A-PB15-Pad28)") (class "Default")
      (node (ref "U1") (pin "28") (pinfunction "PB15_28") (pintype "bidirectional"))
    )
    (net (code "62") (name "unconnected-(U1A-PC6-Pad29)") (class "Default")
      (node (ref "U1") (pin "29") (pinfunction "PC6_29") (pintype "bidirectional"))
    )
    (net (code "63") (name "unconnected-(U1A-PC11-Pad40)") (class "Default")
      (node (ref "U1") (pin "40") (pinfunction "PC11_40") (pintype "bidirectional"))
    )
    (net (code "64") (name "unconnected-(U1A-PC13-Pad2)") (class "Default")
      (node (ref "U1") (pin "2") (pinfunction "PC13_2") (pintype "bidirectional"))
    )
    (net (code "65") (name "unconnected-(U1A-PC14-OSC32_IN-Pad3)") (class "Default")
      (node (ref "U1") (pin "3") (pinfunction "PC14-OSC32_IN_3") (pintype "bidirectional"))
    )
    (net (code "66") (name "unconnected-(U1A-PC15-OSC32_OUT-Pad4)") (class "Default")
      (node (ref "U1") (pin "4") (pinfunction "PC15-OSC32_OUT_4") (pintype "bidirectional"))
    )
    (net (code "67") (name "unconnected-(U2-NC-Pad4)") (class "Default")
      (node (ref "U2") (pin "4") (pinfunction "NC_4") (pintype "passive+no_connect"))
    )
    (net (code "68") (name "unconnected-(U3-IO1-Pad1)") (class "Default")
      (node (ref "U3") (pin "1") (pinfunction "IO1_1") (pintype "passive+no_connect"))
    )
    (net (code "69") (name "unconnected-(U3-IO4-Pad6)") (class "Default")
      (node (ref "U3") (pin "6") (pinfunction "IO4_6") (pintype "passive+no_connect"))
    )
    (net (code "70") (name "unconnected-(U4-CTS-Pad15)") (class "Default")
      (node (ref "U4") (pin "15") (pinfunction "CTS_15") (pintype "passive+no_connect"))
    )
    (net (code "71") (name "unconnected-(U4-DCD-Pad11)") (class "Default")
      (node (ref "U4") (pin "11") (pinfunction "DCD_11") (pintype "passive+no_connect"))
    )
    (net (code "72") (name "unconnected-(U4-DSR-Pad14)") (class "Default")
      (node (ref "U4") (pin "14") (pinfunction "DSR_14") (pintype "passive+no_connect"))
    )
    (net (code "73") (name "unconnected-(U4-RI-Pad16)") (class "Default")
      (node (ref "U4") (pin "16") (pinfunction "RI_16") (pintype "passive+no_connect"))
    )
    (net (code "74") (name "unconnected-(U4-~{ACT}-Pad10)") (class "Default")
      (node (ref "U4") (pin "10") (pinfunction "~{ACT}_10") (pintype "passive+no_connect"))
    )
    (net (code "75") (name "unconnected-(UWB1-EXTON-Pad1)") (class "Default")
      (node (ref "UWB1") (pin "1") (pinfunction "EXTON_1") (pintype "passive+no_connect"))
    )
    (net (code "76") (name "unconnected-(UWB1-GPIO1-Pad14)") (class "Default")
      (node (ref "UWB1") (pin "14") (pinfunction "GPIO1_14") (pintype "passive+no_connect"))
    )
    (net (code "77") (name "unconnected-(UWB1-GPIO4-Pad11)") (class "Default")
      (node (ref "UWB1") (pin "11") (pinfunction "GPIO4_11") (pintype "passive+no_connect"))
    )
    (net (code "78") (name "unconnected-(UWB1-GPIO5-Pad10)") (class "Default")
      (node (ref "UWB1") (pin "10") (pinfunction "GPIO5_10") (pintype "passive+no_connect"))
    )
    (net (code "79") (name "unconnected-(UWB1-GPIO6-Pad9)") (class "Default")
      (node (ref "UWB1") (pin "9") (pinfunction "GPIO6_9") (pintype "passive+no_connect"))
    )
  )
)
